# 2.net
KiCad netlist of a schematic drawn in Altium Designer
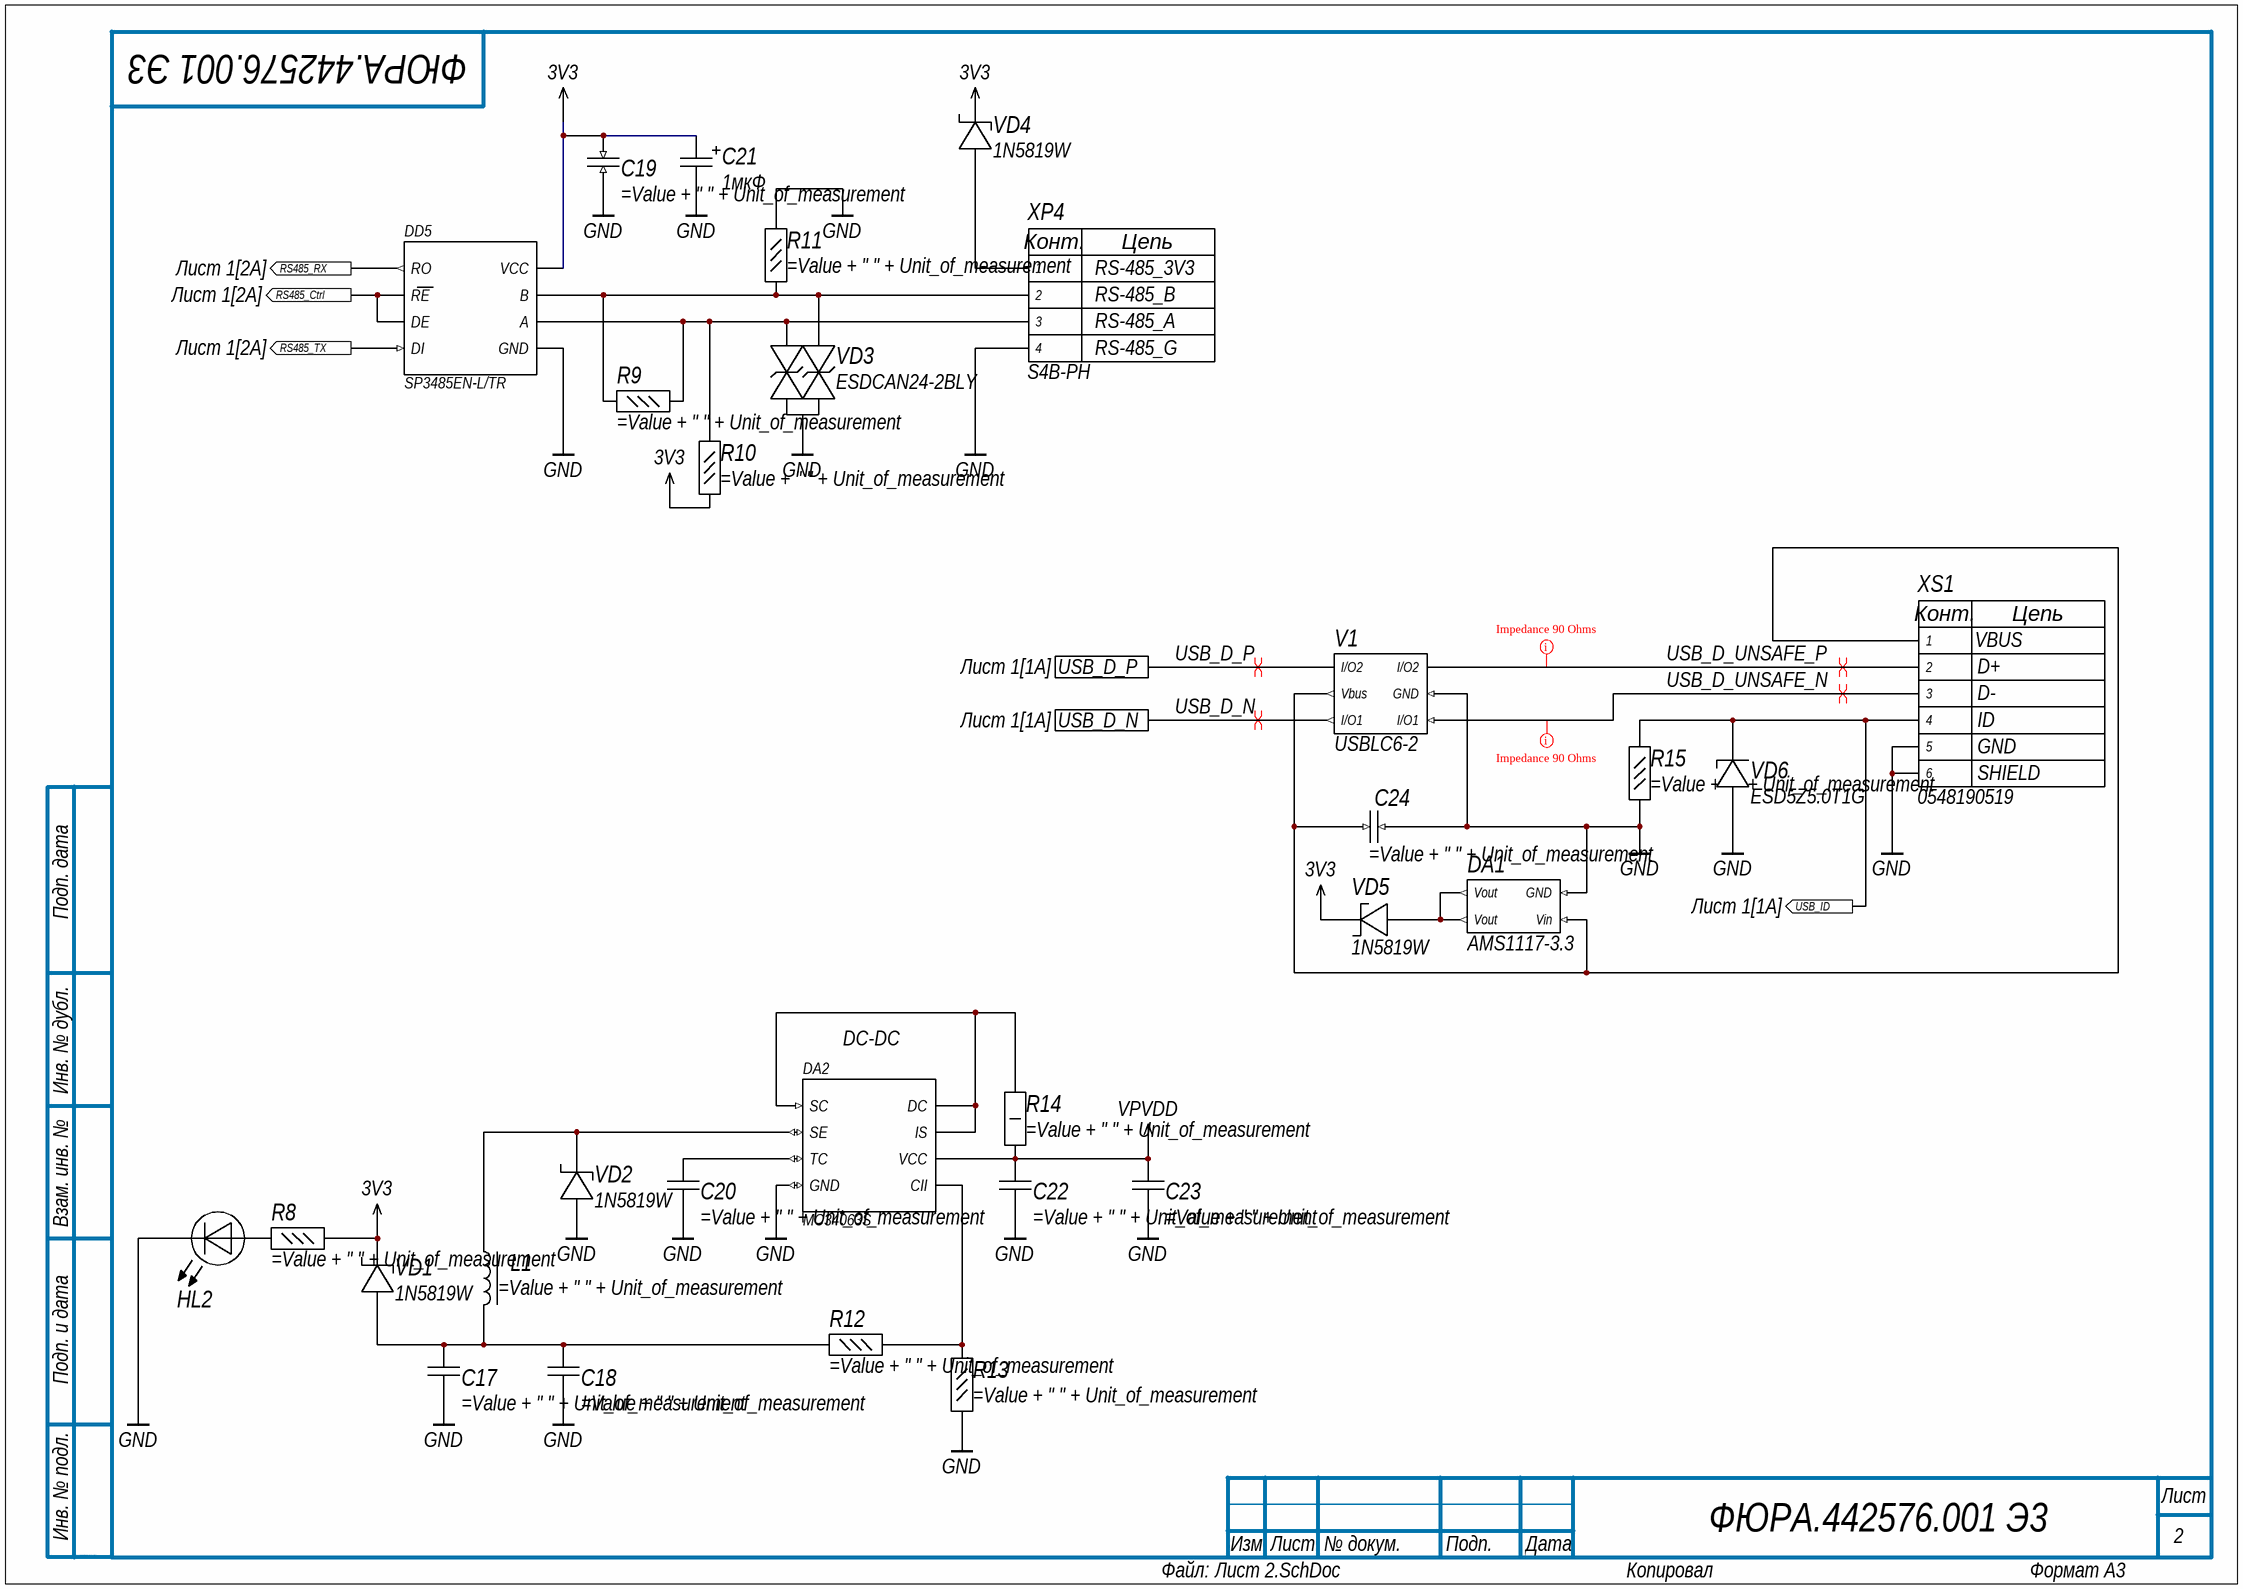
[diagram p0: Лист 2.SchDoc]

(export (version "E")
  (design (tool "Eeschema 10.0.6"))
  (components
    (comp (ref "C17")
      (value "10мкФ 50В")
      (footprint "CAP_1206")
      (description "Конденсатор керамический, типоразмера 1206")
      (libsource (lib "SimpleComponents") (part "CAP_1206"))
    )
    (comp (ref "C18")
      (value "10мкФ 50В")
      (footprint "CAP_1206")
      (description "Конденсатор керамический, типоразмера 1206")
      (libsource (lib "SimpleComponents") (part "CAP_1206"))
    )
    (comp (ref "C19")
      (value "100нФ")
      (footprint "CAP_0603")
      (description "Конденсатор керамический, типоразмера 0603")
      (libsource (lib "PassiveComponents") (part "CAP_0603"))
    )
    (comp (ref "C20")
      (value "10пФ")
      (footprint "CAP_0603")
      (description "Конденсатор керамический, типоразмера 0603")
      (libsource (lib "SimpleComponents") (part "CAP_0603"))
    )
    (comp (ref "C21")
      (value "1мкФ")
      (footprint "TECAP_A")
      (description "Описание свойств компонента")
      (libsource (lib "PassiveComponents") (part "TECAP_A"))
    )
    (comp (ref "C22")
      (value "10мкФ 50В")
      (footprint "CAP_1206")
      (description "Конденсатор керамический, типоразмера 1206")
      (libsource (lib "SimpleComponents") (part "CAP_1206"))
    )
    (comp (ref "C23")
      (value "10мкФ 50В")
      (footprint "CAP_1206")
      (description "Конденсатор керамический, типоразмера 1206")
      (libsource (lib "SimpleComponents") (part "CAP_1206"))
    )
    (comp (ref "C24")
      (value "100нФ")
      (footprint "CAP_0603")
      (description "Конденсатор керамический, типоразмера 0603")
      (libsource (lib "PassiveComponents") (part "CAP_0603"))
    )
    (comp (ref "DA1")
      (value "AMS1117-3.3")
      (footprint "SOT-223")
      (description "Линейный регулятор с малым падением напряжения, 1А, 3.3В [SOT-223]")
      (libsource (lib "ICs") (part "AMS1117-3.3"))
    )
    (comp (ref "DA2")
      (value "MC34063S")
      (footprint "SOP-8 WithoutTP")
      (libsource (lib "ICs") (part "MC34063S"))
    )
    (comp (ref "DD5")
      (value "SP3485EN-L/TR")
      (footprint "SOIC-8 WIthoutTP")
      (description "Трансивер RS485 Half-Duplex 1/1")
      (libsource (lib "ICs") (part "SP3485EN"))
    )
    (comp (ref "HL2") (value "3") (footprint "LED_0805") (libsource (lib "Complicated") (part "LED_0805_R")))
    (comp (ref "L1")
      (value "47мкГн")
      (footprint "CD54")
      (description "Резистор, типоразмера 2010")
      (libsource (lib "SimpleComponents") (part "IND_CD54"))
    )
    (comp (ref "R8")
      (value "330Ом")
      (footprint "RES_0603")
      (description "Резистор, типоразмера 0603")
      (libsource (lib "") (part "RES_0603_3"))
    )
    (comp (ref "R9")
      (value "120Ом")
      (footprint "RES_0603")
      (description "Резистор, типоразмера 0603")
      (libsource (lib "") (part "RES_0603_1"))
    )
    (comp (ref "R10")
      (value "4.7кОм")
      (footprint "RES_0603")
      (description "Резистор, типоразмера 0603")
      (libsource (lib "") (part "RES_0603_2"))
    )
    (comp (ref "R11")
      (value "4.7кОм")
      (footprint "RES_0603")
      (description "Резистор, типоразмера 0603")
      (libsource (lib "SimpleComponents") (part "RES_0603"))
    )
    (comp (ref "R12")
      (value "8.2кОм 1%")
      (footprint "RES_0603")
      (description "Резистор, типоразмера 0603")
      (libsource (lib "") (part "RES_0603_1"))
    )
    (comp (ref "R13")
      (value "4.3кОм 1%")
      (footprint "RES_0603")
      (description "Резистор, типоразмера 0603")
      (libsource (lib "SimpleComponents") (part "RES_0603"))
    )
    (comp (ref "R14")
      (value "0.2Ом 1%")
      (footprint "RES_2512")
      (description "Резистор, типоразмера 2512")
      (libsource (lib "SimpleComponents") (part "RES_2512"))
    )
    (comp (ref "R15")
      (value "100кОм")
      (footprint "RES_0603")
      (description "Резистор, типоразмера 0603")
      (libsource (lib "SimpleComponents") (part "RES_0603"))
    )
    (comp (ref "V1")
      (value "USBLC6-2")
      (footprint "SOT23-6")
      (description "Защита интерфейса USB от электростатических разрядов [SOT-23-6]")
      (libsource (lib "ICs") (part "USBLC6-2"))
    )
    (comp (ref "VD1")
      (value "1N5819W")
      (footprint "SOD-123")
      (description "Диод Шоттки, 40 В, 0.35 А, SOD-123")
      (libsource (lib "SimpleComponents") (part "1N5819W"))
    )
    (comp (ref "VD2")
      (value "1N5819W")
      (footprint "SOD-123")
      (description "Диод Шоттки, 40 В, 0.35 А, SOD-123")
      (libsource (lib "SimpleComponents") (part "1N5819W"))
    )
    (comp (ref "VD3")
      (value "ESDCAN24-2BLY")
      (footprint "SOT23")
      (description "Устройство защиты CAN шины от ESD, 2 защитных диода [SOT-23-3]")
      (libsource (lib "Complicated") (part "ESDCAN24-2BLY"))
    )
    (comp (ref "VD4")
      (value "1N5819W")
      (footprint "SOD-123")
      (description "Диод Шоттки, 40 В, 0.35 А, SOD-123")
      (libsource (lib "SimpleComponents") (part "1N5819W"))
    )
    (comp (ref "VD5")
      (value "1N5819W")
      (footprint "SOD-123")
      (description "Диод Шоттки, 40 В, 0.35 А, SOD-123")
      (libsource (lib "Complicated") (part "1N5819W"))
    )
    (comp (ref "VD6")
      (value "ESD5Z5.0T1G")
      (footprint "SOD-523")
      (description "Устройство защиты от ESD, защитный диод, 5В [SOD-523]")
      (libsource (lib "Complicated") (part "ESD5Z5.0T1G"))
    )
    (comp (ref "XP4")
      (value "S4B-PH")
      (footprint "S4B-PH")
      (description "JST PH 4pin 2 mm pitch; horizontal; through hole OR full smd; S4B-PH-SM4-TB")
      (libsource (lib "SimpleComponents") (part "S4B-PH"))
    )
    (comp (ref "XS1")
      (value "0548190519")
      (footprint "USB_Mini_B_TH")
      (description "USB - mini B USB 2.0 OTG Receptacle Connector 5 Position Through Hole, Right Angle")
      (libsource (lib "SimpleComponents") (part "0548190519"))
    )
  )
  (nets
    (net (code "1") (name "/RS485_Ctrl") (class "Default")
      (node (ref "DD5") (pin "2") (pinfunction "RE_2") (pintype "passive"))
      (node (ref "DD5") (pin "3") (pinfunction "DE_3") (pintype "passive"))
    )
    (net (code "2") (name "/RS485_RX") (class "Default")
      (node (ref "DD5") (pin "1") (pinfunction "RO_1") (pintype "output"))
    )
    (net (code "3") (name "/RS485_TX") (class "Default")
      (node (ref "DD5") (pin "4") (pinfunction "DI_4") (pintype "input"))
    )
    (net (code "4") (name "/USB_D_N") (class "Default")
      (node (ref "V1") (pin "6") (pinfunction "I/O1_6") (pintype "output"))
    )
    (net (code "5") (name "/USB_D_P") (class "Default")
      (node (ref "V1") (pin "4") (pinfunction "I/O2_4") (pintype "power_in"))
    )
    (net (code "6") (name "/USB_D_UNSAFE_N") (class "Default")
      (node (ref "V1") (pin "1") (pinfunction "I/O1_1") (pintype "input"))
      (node (ref "XS1") (pin "4") (pinfunction "3_4") (pintype "passive"))
    )
    (net (code "7") (name "/USB_D_UNSAFE_P") (class "Default")
      (node (ref "V1") (pin "3") (pinfunction "I/O2_3") (pintype "power_in"))
      (node (ref "XS1") (pin "3") (pinfunction "2_3") (pintype "passive"))
    )
    (net (code "8") (name "/USB_ID") (class "Default")
      (node (ref "R15") (pin "2") (pinfunction "2_2") (pintype "passive"))
      (node (ref "VD6") (pin "1") (pinfunction "1_1") (pintype "passive"))
      (node (ref "XS1") (pin "2") (pinfunction "4_2") (pintype "passive"))
    )
    (net (code "9") (name "3V3") (class "Default")
      (node (ref "C19") (pin "2") (pintype "input"))
      (node (ref "C21") (pin "1") (pintype "passive"))
      (node (ref "DD5") (pin "8") (pinfunction "VCC_8") (pintype "power_in"))
      (node (ref "R10") (pin "2") (pinfunction "2_2") (pintype "passive"))
      (node (ref "R8") (pin "1") (pinfunction "1_1") (pintype "passive"))
      (node (ref "VD1") (pin "1") (pinfunction "1_1") (pintype "passive"))
      (node (ref "VD4") (pin "1") (pinfunction "1_1") (pintype "passive"))
      (node (ref "VD5") (pin "1") (pinfunction "1_1") (pintype "passive"))
    )
    (net (code "10") (name "GND") (class "Default")
      (node (ref "C17") (pin "1") (pintype "passive"))
      (node (ref "C18") (pin "1") (pintype "passive"))
      (node (ref "C19") (pin "1") (pintype "input"))
      (node (ref "C20") (pin "1") (pintype "passive"))
      (node (ref "C21") (pin "2") (pintype "passive"))
      (node (ref "C22") (pin "1") (pintype "passive"))
      (node (ref "C23") (pin "1") (pintype "passive"))
      (node (ref "C24") (pin "1") (pintype "input"))
      (node (ref "DA1") (pin "1") (pinfunction "GND_1") (pintype "input"))
      (node (ref "DA2") (pin "4") (pinfunction "GND_4") (pintype "bidirectional"))
      (node (ref "DD5") (pin "5") (pinfunction "GND_5") (pintype "power_in"))
      (node (ref "HL2") (pin "C") (pinfunction "1_C") (pintype "passive"))
      (node (ref "R11") (pin "2") (pinfunction "2_2") (pintype "passive"))
      (node (ref "R13") (pin "1") (pinfunction "1_1") (pintype "passive"))
      (node (ref "R15") (pin "1") (pinfunction "1_1") (pintype "passive"))
      (node (ref "V1") (pin "2") (pinfunction "GND_2") (pintype "input"))
      (node (ref "VD2") (pin "2") (pinfunction "2_2") (pintype "passive"))
      (node (ref "VD3") (pin "3") (pinfunction "3_3") (pintype "passive"))
      (node (ref "VD6") (pin "2") (pinfunction "2_2") (pintype "passive"))
      (node (ref "XP4") (pin "4") (pinfunction "4_4") (pintype "passive"))
      (node (ref "XS1") (pin "1") (pinfunction "5_1") (pintype "passive"))
      (node (ref "XS1") (pin "6") (pinfunction "6_6") (pintype "passive"))
    )
    (net (code "11") (name "Net-(C17-Pad2)") (class "Default")
      (node (ref "C17") (pin "2") (pintype "passive"))
      (node (ref "C18") (pin "2") (pintype "passive"))
      (node (ref "L1") (pin "2") (pinfunction "2_2") (pintype "passive"))
      (node (ref "R12") (pin "1") (pinfunction "1_1") (pintype "passive"))
      (node (ref "VD1") (pin "2") (pinfunction "2_2") (pintype "passive"))
    )
    (net (code "12") (name "Net-(DA1-Vin)") (class "Default")
      (node (ref "C24") (pin "2") (pintype "input"))
      (node (ref "DA1") (pin "3") (pinfunction "Vin_3") (pintype "input"))
      (node (ref "V1") (pin "5") (pinfunction "Vbus_5") (pintype "output"))
      (node (ref "XS1") (pin "5") (pinfunction "1_5") (pintype "passive"))
    )
    (net (code "13") (name "Net-(DA1-Vout-Pad2)") (class "Default")
      (node (ref "DA1") (pin "2") (pinfunction "Vout_2") (pintype "output"))
      (node (ref "DA1") (pin "4") (pinfunction "Vout_4") (pintype "output"))
      (node (ref "VD5") (pin "2") (pinfunction "2_2") (pintype "passive"))
    )
    (net (code "14") (name "Net-(DA2-CII)") (class "Default")
      (node (ref "DA2") (pin "5") (pinfunction "CII_5") (pintype "power_in"))
      (node (ref "R12") (pin "2") (pinfunction "2_2") (pintype "passive"))
      (node (ref "R13") (pin "2") (pinfunction "2_2") (pintype "passive"))
    )
    (net (code "15") (name "Net-(DA2-DC)") (class "Default")
      (node (ref "DA2") (pin "1") (pinfunction "SC_1") (pintype "input"))
      (node (ref "DA2") (pin "7") (pinfunction "IS_7") (pintype "power_in"))
      (node (ref "DA2") (pin "8") (pinfunction "DC_8") (pintype "power_in"))
      (node (ref "R14") (pin "2") (pinfunction "2_2") (pintype "passive"))
    )
    (net (code "16") (name "Net-(DA2-SE)") (class "Default")
      (node (ref "DA2") (pin "2") (pinfunction "SE_2") (pintype "bidirectional"))
      (node (ref "L1") (pin "1") (pinfunction "1_1") (pintype "passive"))
      (node (ref "VD2") (pin "1") (pinfunction "1_1") (pintype "passive"))
    )
    (net (code "17") (name "Net-(DA2-TC)") (class "Default")
      (node (ref "C20") (pin "2") (pintype "passive"))
      (node (ref "DA2") (pin "3") (pinfunction "TC_3") (pintype "bidirectional"))
    )
    (net (code "18") (name "Net-(DD5-A)") (class "Default")
      (node (ref "DD5") (pin "6") (pinfunction "A_6") (pintype "power_in"))
      (node (ref "R10") (pin "1") (pinfunction "1_1") (pintype "passive"))
      (node (ref "R9") (pin "2") (pinfunction "2_2") (pintype "passive"))
      (node (ref "VD3") (pin "2") (pinfunction "2_2") (pintype "passive"))
      (node (ref "XP4") (pin "3") (pinfunction "3_3") (pintype "passive"))
    )
    (net (code "19") (name "Net-(DD5-B)") (class "Default")
      (node (ref "DD5") (pin "7") (pinfunction "B_7") (pintype "power_in"))
      (node (ref "R11") (pin "1") (pinfunction "1_1") (pintype "passive"))
      (node (ref "R9") (pin "1") (pinfunction "1_1") (pintype "passive"))
      (node (ref "VD3") (pin "1") (pinfunction "1_1") (pintype "passive"))
      (node (ref "XP4") (pin "2") (pinfunction "2_2") (pintype "passive"))
    )
    (net (code "20") (name "Net-(HL2-2)") (class "Default")
      (node (ref "HL2") (pin "A") (pinfunction "2_A") (pintype "passive"))
      (node (ref "R8") (pin "2") (pinfunction "2_2") (pintype "passive"))
    )
    (net (code "21") (name "Net-(VD4-Pad2)") (class "Default")
      (node (ref "VD4") (pin "2") (pinfunction "2_2") (pintype "passive"))
      (node (ref "XP4") (pin "1") (pinfunction "1_1") (pintype "passive"))
    )
    (net (code "22") (name "VPVDD") (class "Default")
      (node (ref "C22") (pin "2") (pintype "passive"))
      (node (ref "C23") (pin "2") (pintype "passive"))
      (node (ref "DA2") (pin "6") (pinfunction "VCC_6") (pintype "power_in"))
      (node (ref "R14") (pin "1") (pinfunction "1_1") (pintype "passive"))
    )
  )
)
